# CH32V307VCT6-R0.net
KiCad netlist of a schematic drawn in Altium Designer
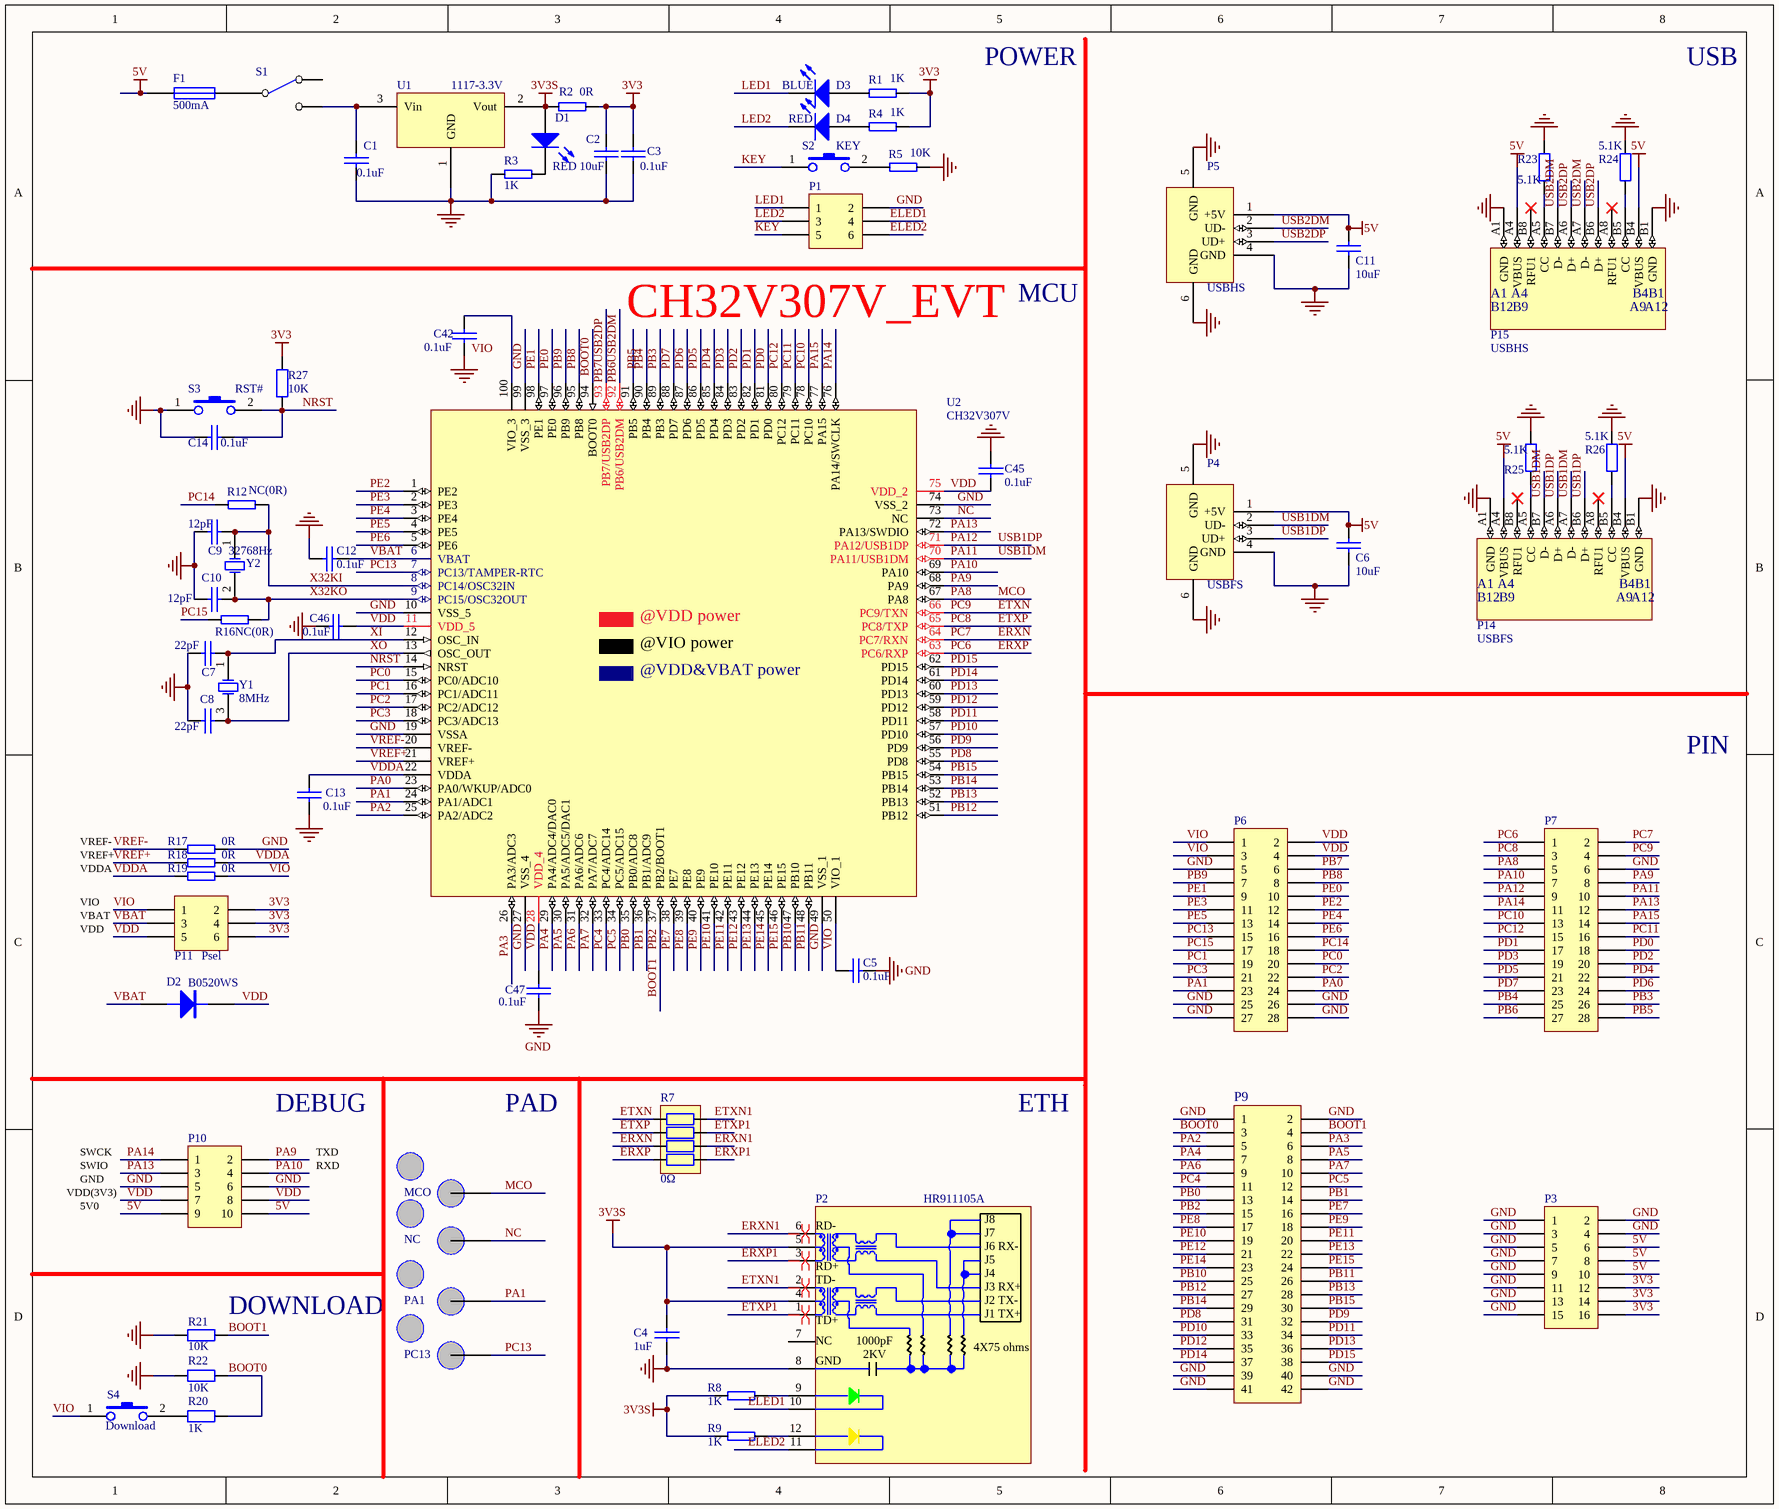
[diagram p0: CH32V307VCT6-R0.SchDoc]

(export (version "E")
  (design (tool "Eeschema 10.0.6"))
  (components
    (comp (ref "C1")
      (value "0.1uF")
      (footprint "0603_C")
      (description "Capacitor")
      (libsource (lib "*") (part "CAP"))
    )
    (comp (ref "C2")
      (value "10uF")
      (footprint "3216_C")
      (description "Capacitor")
      (libsource (lib "*") (part "CAP"))
    )
    (comp (ref "C3")
      (value "0.1uF")
      (footprint "0603_C")
      (description "Capacitor")
      (libsource (lib "*") (part "CAP"))
    )
    (comp (ref "C4")
      (value "1uF")
      (footprint "0603_C")
      (description "Capacitor")
      (libsource (lib "*") (part "CAP"))
    )
    (comp (ref "C5")
      (value "0.1uF")
      (footprint "0603_C")
      (description "Capacitor")
      (libsource (lib "*") (part "CAP"))
    )
    (comp (ref "C6")
      (value "10uF")
      (footprint "3216_C")
      (description "Capacitor")
      (libsource (lib "") (part "CAP_1"))
    )
    (comp (ref "C7")
      (value "22pF")
      (footprint "0603_C")
      (description "Capacitor")
      (libsource (lib "*") (part "CAP"))
    )
    (comp (ref "C8")
      (value "22pF")
      (footprint "0603_C")
      (description "Capacitor")
      (libsource (lib "*") (part "CAP"))
    )
    (comp (ref "C9")
      (value "12pF")
      (footprint "0603_C")
      (description "Capacitor")
      (libsource (lib "*") (part "CAP"))
    )
    (comp (ref "C10")
      (value "12pF")
      (footprint "0603_C")
      (description "Capacitor")
      (libsource (lib "*") (part "CAP"))
    )
    (comp (ref "C11")
      (value "10uF")
      (footprint "3216_C")
      (description "Capacitor")
      (libsource (lib "") (part "CAP_1"))
    )
    (comp (ref "C12")
      (value "0.1uF")
      (footprint "0603_C")
      (description "Capacitor")
      (libsource (lib "*") (part "CAP"))
    )
    (comp (ref "C13")
      (value "0.1uF")
      (footprint "0603_C")
      (description "Capacitor")
      (libsource (lib "*") (part "CAP"))
    )
    (comp (ref "C14")
      (value "0.1uF")
      (footprint "0603_C")
      (description "Capacitor")
      (libsource (lib "") (part "CAP_1"))
    )
    (comp (ref "C42")
      (value "0.1uF")
      (footprint "0603_C")
      (description "Capacitor")
      (libsource (lib "*") (part "CAP"))
    )
    (comp (ref "C45")
      (value "0.1uF")
      (footprint "0603_C")
      (description "Capacitor")
      (libsource (lib "*") (part "CAP"))
    )
    (comp (ref "C46")
      (value "0.1uF")
      (footprint "0603_C")
      (description "Capacitor")
      (libsource (lib "*") (part "CAP"))
    )
    (comp (ref "C47")
      (value "0.1uF")
      (footprint "0603_C")
      (description "Capacitor")
      (libsource (lib "*") (part "CAP"))
    )
    (comp (ref "D1")
      (value "RED")
      (footprint "0603+")
      (description "Typical INFRARED GaAs LED")
      (fields (field (name "PUBLISHER") "Altium Limited"))
      (libsource (lib "*") (part "LED0"))
    )
    (comp (ref "D2")
      (value "B0520WS")
      (footprint "SOD-323")
      (description "Diode")
      (libsource (lib "*") (part "DIODE"))
    )
    (comp (ref "D3")
      (value "BLUE")
      (footprint "0603+")
      (description "Typical INFRARED GaAs LED")
      (fields (field (name "PUBLISHER") "Altium Limited"))
      (libsource (lib "*") (part "LED0"))
    )
    (comp (ref "D4")
      (value "RED")
      (footprint "0603+")
      (description "Typical INFRARED GaAs LED")
      (fields (field (name "PUBLISHER") "Altium Limited"))
      (libsource (lib "*") (part "LED0"))
    )
    (comp (ref "F1")
      (value "500mA")
      (footprint "0805")
      (description "Fuse")
      (libsource (lib "wch_sch_others") (part "FUSE1"))
    )
    (comp (ref "MCO")
      (value "Testpoint")
      (footprint "TESTPOINT1")
      (description "测试点")
      (libsource (lib "wch_sch_others") (part "Testpoint"))
    )
    (comp (ref "NC")
      (value "Testpoint")
      (footprint "TESTPOINT1")
      (description "测试点")
      (libsource (lib "wch_sch_others") (part "Testpoint"))
    )
    (comp (ref "P1")
      (value "IO")
      (footprint "IDC6-2.54mm")
      (description "Header, 3-Pin, Dual row, Right Angle")
      (fields (field (name "PUBLISHER") "Altium Limited"))
      (libsource (lib "Miscellaneous Connectors") (part "Header 3X2H"))
    )
    (comp (ref "P2") (value "HR911105A") (footprint "HR911105A") (libsource (lib "*") (part "HR911105A")))
    (comp (ref "P3")
      (value "Ppin")
      (footprint "IDC16-2.54mm")
      (description "Header, 8-Pin, Dual row, Right Angle")
      (fields (field (name "PUBLISHER") "Altium Limited"))
      (libsource (lib "Miscellaneous Connectors") (part "Header 8X2H"))
    )
    (comp (ref "P4")
      (value "USBFS")
      (footprint "USBAF")
      (description "USB Port")
      (libsource (lib "*") (part "USB"))
    )
    (comp (ref "P5")
      (value "USBHS")
      (footprint "USBAF")
      (description "USB Port")
      (libsource (lib "*") (part "USB"))
    )
    (comp (ref "P6")
      (value "HEADER 14x2")
      (footprint "MYPCB:IDC28-2.54MM")
      (description "Header, 14-Pin, Dual row")
      (libsource (lib "wch_sch_others") (part "HEADER 14x2"))
    )
    (comp (ref "P7")
      (value "HEADER 14x2")
      (footprint "MYPCB:IDC28-2.54MM")
      (description "Header, 14-Pin, Dual row")
      (libsource (lib "wch_sch_others") (part "HEADER 14x2"))
    )
    (comp (ref "P9")
      (value "HEADER 21x2")
      (footprint "MYPCB:IDC42-2.54MM")
      (description "Header, 21-Pin, Dual row")
      (libsource (lib "wch_sch_others") (part "HEADER 21x2"))
    )
    (comp (ref "P10")
      (value "LINK")
      (footprint "IDC10-2.54mm")
      (description "Header, 5-Pin, Dual row, Right Angle")
      (fields (field (name "PUBLISHER") "Altium Limited"))
      (libsource (lib "Miscellaneous Connectors") (part "Header 5X2H"))
    )
    (comp (ref "P11")
      (value "Psel")
      (footprint "IDC6-2.54mm")
      (description "Header, 3-Pin, Dual row, Right Angle")
      (fields (field (name "PUBLISHER") "Altium Limited"))
      (libsource (lib "Miscellaneous Connectors") (part "Header 3X2H"))
    )
    (comp (ref "P14")
      (value "USBFS")
      (footprint "TYPE-C-Receptacle-2.0")
      (libsource (lib "*") (part "TYPE-C1"))
    )
    (comp (ref "P15")
      (value "USBHS")
      (footprint "TYPE-C-Receptacle-2.0")
      (libsource (lib "*") (part "TYPE-C1"))
    )
    (comp (ref "PA1")
      (value "Testpoint")
      (footprint "TESTPOINT1")
      (description "测试点")
      (libsource (lib "wch_sch_others") (part "Testpoint"))
    )
    (comp (ref "PC13")
      (value "Testpoint")
      (footprint "TESTPOINT1")
      (description "测试点")
      (libsource (lib "wch_sch_others") (part "Testpoint"))
    )
    (comp (ref "R1") (value "1K") (footprint "0603") (libsource (lib "wch_sch_others") (part "RES")))
    (comp (ref "R2") (value "0R") (footprint "0603") (libsource (lib "wch_sch_others") (part "RES")))
    (comp (ref "R3") (value "1K") (footprint "0603") (libsource (lib "wch_sch_others") (part "RES")))
    (comp (ref "R4") (value "1K") (footprint "0603") (libsource (lib "wch_sch_others") (part "RES")))
    (comp (ref "R5") (value "10K") (footprint "0603") (libsource (lib "wch_sch_others") (part "RES")))
    (comp (ref "R7")
      (value "0Ω")
      (footprint "RCA-8P4R-0603")
      (description "贴片网络排阻")
      (fields (field (name "版权归属") "源创客"))
      (libsource (lib "wch_sch_others") (part "R-8P4R"))
    )
    (comp (ref "R8") (value "1K") (footprint "0603") (libsource (lib "wch_sch_others") (part "RES")))
    (comp (ref "R9") (value "1K") (footprint "0603") (libsource (lib "wch_sch_others") (part "RES")))
    (comp (ref "R12") (value "NC(0R)") (footprint "0603") (libsource (lib "wch_sch_others") (part "RES")))
    (comp (ref "R16") (value "NC(0R)") (footprint "0603") (libsource (lib "wch_sch_others") (part "RES")))
    (comp (ref "R17") (value "0R") (footprint "0603") (libsource (lib "*") (part "R")))
    (comp (ref "R18") (value "0R") (footprint "0603") (libsource (lib "*") (part "R")))
    (comp (ref "R19") (value "0R") (footprint "0603") (libsource (lib "*") (part "R")))
    (comp (ref "R20")
      (value "1K")
      (footprint "0603")
      (description "Resistor")
      (fields (field (name "PUBLISHER") "Altium Limited"))
      (libsource (lib "") (part "Res2_1"))
    )
    (comp (ref "R21")
      (value "10K")
      (footprint "0603")
      (description "Resistor")
      (fields (field (name "PUBLISHER") "Altium Limited"))
      (libsource (lib "") (part "Res2_1"))
    )
    (comp (ref "R22")
      (value "10K")
      (footprint "0603")
      (description "Resistor")
      (fields (field (name "PUBLISHER") "Altium Limited"))
      (libsource (lib "") (part "Res2_1"))
    )
    (comp (ref "R23")
      (value "5.1K")
      (footprint "0603")
      (description "Resistor")
      (libsource (lib "Miscellaneous Devices") (part "Res2"))
    )
    (comp (ref "R24")
      (value "5.1K")
      (footprint "0603")
      (description "Resistor")
      (libsource (lib "Miscellaneous Devices") (part "Res2"))
    )
    (comp (ref "R25")
      (value "5.1K")
      (footprint "0603")
      (description "Resistor")
      (libsource (lib "Miscellaneous Devices") (part "Res2"))
    )
    (comp (ref "R26")
      (value "5.1K")
      (footprint "0603")
      (description "Resistor")
      (libsource (lib "Miscellaneous Devices") (part "Res2"))
    )
    (comp (ref "R27")
      (value "10K")
      (footprint "0603")
      (description "Resistor")
      (fields (field (name "PUBLISHER") "Altium Limited"))
      (libsource (lib "Miscellaneous Devices") (part "Res2"))
    )
    (comp (ref "S1") (value "SW SPDT") (footprint "KEY_B") (libsource (lib "*") (part "SW SPDT")))
    (comp (ref "S2")
      (value "KEY")
      (footprint "SMD_6.1x3.65x2.5mm-KEY")
      (libsource (lib "wch_sch_others") (part "KEY1"))
    )
    (comp (ref "S3")
      (value "RST#")
      (footprint "SMD_6.1x3.65x2.5mm-KEY")
      (libsource (lib "wch_sch_others") (part "KEY1"))
    )
    (comp (ref "S4")
      (value "Download")
      (footprint "SMD_6.1x3.65x2.5mm-KEY")
      (libsource (lib "wch_sch_others") (part "KEY1"))
    )
    (comp (ref "U1")
      (value "1117-3.3V")
      (footprint "SOT-223")
      (libsource (lib "wch_sch_others") (part "1117-3.3V"))
    )
    (comp (ref "U2")
      (value "CH32V307V")
      (footprint "LQFP100")
      (description "RISC-V FPU HD-MCU, 144MHz, USB_480M, USB OTG, 1000M Ethernet MAC, 2*CAN, FSMC+DVP")
      (libsource (lib "CHXXX") (part "CH32V307V"))
    )
    (comp (ref "Y1")
      (value "8MHz")
      (footprint "XT3225")
      (description "Crystal Oscillator")
      (fields (field (name "PUBLISHER") "Altium Limited"))
      (libsource (lib "*") (part "XTAL"))
    )
    (comp (ref "Y2")
      (value "32768Hz")
      (footprint "FC-135")
      (description "Crystal Oscillator")
      (fields (field (name "PUBLISHER") "Altium Limited"))
      (libsource (lib "") (part "XTAL_1"))
    )
  )
  (nets
    (net (code "2") (name "/BOOT0") (class "Default")
      (node (ref "P9") (pin "3") (pinfunction "3_3") (pintype "passive"))
      (node (ref "R20") (pin "1") (pinfunction "1_1") (pintype "passive"))
      (node (ref "R22") (pin "1") (pinfunction "1_1") (pintype "passive"))
      (node (ref "U2") (pin "94") (pinfunction "BOOT0_94") (pintype "input"))
    )
    (net (code "3") (name "/BOOT1") (class "Default")
      (node (ref "P9") (pin "15") (pinfunction "15_15") (pintype "passive"))
      (node (ref "P9") (pin "4") (pinfunction "4_4") (pintype "passive"))
      (node (ref "R21") (pin "1") (pinfunction "1_1") (pintype "passive"))
      (node (ref "U2") (pin "37") (pinfunction "PB2/BOOT1_37") (pintype "bidirectional"))
    )
    (net (code "4") (name "/ELED1") (class "Default")
      (node (ref "P1") (pin "4") (pinfunction "4_4") (pintype "passive"))
      (node (ref "P2") (pin "10") (pintype "passive"))
    )
    (net (code "5") (name "/ELED2") (class "Default")
      (node (ref "P1") (pin "6") (pinfunction "6_6") (pintype "passive"))
      (node (ref "P2") (pin "11") (pintype "passive"))
    )
    (net (code "6") (name "/ERXN") (class "Default")
      (node (ref "P7") (pin "2") (pinfunction "2_2") (pintype "passive"))
      (node (ref "R7") (pin "3") (pinfunction "3_3") (pintype "passive"))
      (node (ref "U2") (pin "64") (pinfunction "PC7/RXN_64") (pintype "bidirectional"))
    )
    (net (code "7") (name "/ERXN1") (class "Default")
      (node (ref "P2") (pin "6") (pintype "passive"))
      (node (ref "R7") (pin "6") (pinfunction "6_6") (pintype "passive"))
    )
    (net (code "8") (name "/ERXP") (class "Default")
      (node (ref "P7") (pin "1") (pinfunction "1_1") (pintype "passive"))
      (node (ref "R7") (pin "4") (pinfunction "4_4") (pintype "passive"))
      (node (ref "U2") (pin "63") (pinfunction "PC6/RXP_63") (pintype "bidirectional"))
    )
    (net (code "9") (name "/ERXP1") (class "Default")
      (node (ref "P2") (pin "3") (pintype "passive"))
      (node (ref "R7") (pin "5") (pinfunction "5_5") (pintype "passive"))
    )
    (net (code "10") (name "/ETXN") (class "Default")
      (node (ref "P7") (pin "4") (pinfunction "4_4") (pintype "passive"))
      (node (ref "R7") (pin "1") (pinfunction "1_1") (pintype "passive"))
      (node (ref "U2") (pin "66") (pinfunction "PC9/TXN_66") (pintype "bidirectional"))
    )
    (net (code "11") (name "/ETXN1") (class "Default")
      (node (ref "P2") (pin "2") (pintype "passive"))
      (node (ref "R7") (pin "8") (pinfunction "8_8") (pintype "passive"))
    )
    (net (code "12") (name "/ETXP") (class "Default")
      (node (ref "P7") (pin "3") (pinfunction "3_3") (pintype "passive"))
      (node (ref "R7") (pin "2") (pinfunction "2_2") (pintype "passive"))
      (node (ref "U2") (pin "65") (pinfunction "PC8/TXP_65") (pintype "bidirectional"))
    )
    (net (code "13") (name "/ETXP1") (class "Default")
      (node (ref "P2") (pin "1") (pintype "passive"))
      (node (ref "R7") (pin "7") (pinfunction "7_7") (pintype "passive"))
    )
    (net (code "14") (name "/KEY") (class "Default")
      (node (ref "P1") (pin "5") (pinfunction "5_5") (pintype "passive"))
      (node (ref "S2") (pin "1") (pinfunction "1_1") (pintype "passive"))
    )
    (net (code "15") (name "/LED1") (class "Default")
      (node (ref "D3") (pin "2") (pinfunction "K_2") (pintype "passive"))
      (node (ref "P1") (pin "1") (pinfunction "1_1") (pintype "passive"))
    )
    (net (code "16") (name "/LED2") (class "Default")
      (node (ref "D4") (pin "2") (pinfunction "K_2") (pintype "passive"))
      (node (ref "P1") (pin "3") (pinfunction "3_3") (pintype "passive"))
    )
    (net (code "17") (name "/MCO") (class "Default")
      (node (ref "MCO") (pin "1") (pinfunction "point_1") (pintype "passive"))
      (node (ref "P7") (pin "5") (pinfunction "5_5") (pintype "passive"))
      (node (ref "U2") (pin "67") (pinfunction "PA8_67") (pintype "bidirectional"))
    )
    (net (code "18") (name "/NC") (class "Default")
      (node (ref "NC") (pin "1") (pinfunction "point_1") (pintype "passive"))
      (node (ref "U2") (pin "73") (pinfunction "NC_73") (pintype "tri_state"))
    )
    (net (code "19") (name "/NRST") (class "Default")
      (node (ref "C14") (pin "2") (pinfunction "2_2") (pintype "passive"))
      (node (ref "R27") (pin "1") (pinfunction "1_1") (pintype "passive"))
      (node (ref "S3") (pin "2") (pinfunction "2_2") (pintype "passive"))
      (node (ref "U2") (pin "14") (pinfunction "NRST_14") (pintype "input"))
    )
    (net (code "20") (name "/PA0") (class "Default")
      (node (ref "P6") (pin "24") (pinfunction "24_24") (pintype "passive"))
      (node (ref "U2") (pin "23") (pinfunction "PA0/WKUP/ADC0_23") (pintype "bidirectional"))
    )
    (net (code "21") (name "/PA1") (class "Default")
      (node (ref "P6") (pin "23") (pinfunction "23_23") (pintype "passive"))
      (node (ref "PA1") (pin "1") (pinfunction "point_1") (pintype "passive"))
      (node (ref "U2") (pin "24") (pinfunction "PA1/ADC1_24") (pintype "bidirectional"))
    )
    (net (code "22") (name "/PA2") (class "Default")
      (node (ref "P9") (pin "5") (pinfunction "5_5") (pintype "passive"))
      (node (ref "U2") (pin "25") (pinfunction "PA2/ADC2_25") (pintype "bidirectional"))
    )
    (net (code "23") (name "/PA3") (class "Default")
      (node (ref "P9") (pin "6") (pinfunction "6_6") (pintype "passive"))
      (node (ref "U2") (pin "26") (pinfunction "PA3/ADC3_26") (pintype "bidirectional"))
    )
    (net (code "24") (name "/PA4") (class "Default")
      (node (ref "P9") (pin "7") (pinfunction "7_7") (pintype "passive"))
      (node (ref "U2") (pin "29") (pinfunction "PA4/ADC4/DAC0_29") (pintype "bidirectional"))
    )
    (net (code "25") (name "/PA5") (class "Default")
      (node (ref "P9") (pin "8") (pinfunction "8_8") (pintype "passive"))
      (node (ref "U2") (pin "30") (pinfunction "PA5/ADC5/DAC1_30") (pintype "bidirectional"))
    )
    (net (code "26") (name "/PA6") (class "Default")
      (node (ref "P9") (pin "9") (pinfunction "9_9") (pintype "passive"))
      (node (ref "U2") (pin "31") (pinfunction "PA6/ADC6_31") (pintype "bidirectional"))
    )
    (net (code "27") (name "/PA7") (class "Default")
      (node (ref "P9") (pin "10") (pinfunction "10_10") (pintype "passive"))
      (node (ref "U2") (pin "32") (pinfunction "PA7/ADC7_32") (pintype "bidirectional"))
    )
    (net (code "28") (name "/PA9") (class "Default")
      (node (ref "P10") (pin "2") (pinfunction "2_2") (pintype "passive"))
      (node (ref "P7") (pin "8") (pinfunction "8_8") (pintype "passive"))
      (node (ref "U2") (pin "68") (pinfunction "PA9_68") (pintype "bidirectional"))
    )
    (net (code "29") (name "/PA10") (class "Default")
      (node (ref "P10") (pin "4") (pinfunction "4_4") (pintype "passive"))
      (node (ref "P7") (pin "7") (pinfunction "7_7") (pintype "passive"))
      (node (ref "U2") (pin "69") (pinfunction "PA10_69") (pintype "bidirectional"))
    )
    (net (code "30") (name "/PA11") (class "Default")
      (node (ref "P14") (pin "A7") (pinfunction "D-_A7") (pintype "bidirectional"))
      (node (ref "P14") (pin "B7") (pinfunction "D-_B7") (pintype "bidirectional"))
      (node (ref "P4") (pin "2") (pinfunction "UD-_2") (pintype "bidirectional"))
      (node (ref "P7") (pin "10") (pinfunction "10_10") (pintype "passive"))
      (node (ref "U2") (pin "70") (pinfunction "PA11/USB1DM_70") (pintype "bidirectional"))
    )
    (net (code "31") (name "/PA12") (class "Default")
      (node (ref "P14") (pin "A6") (pinfunction "D+_A6") (pintype "bidirectional"))
      (node (ref "P14") (pin "B6") (pinfunction "D+_B6") (pintype "bidirectional"))
      (node (ref "P4") (pin "3") (pinfunction "UD+_3") (pintype "bidirectional"))
      (node (ref "P7") (pin "9") (pinfunction "9_9") (pintype "passive"))
      (node (ref "U2") (pin "71") (pinfunction "PA12/USB1DP_71") (pintype "bidirectional"))
    )
    (net (code "32") (name "/PA13") (class "Default")
      (node (ref "P10") (pin "3") (pinfunction "3_3") (pintype "passive"))
      (node (ref "P7") (pin "12") (pinfunction "12_12") (pintype "passive"))
      (node (ref "U2") (pin "72") (pinfunction "PA13/SWDIO_72") (pintype "bidirectional"))
    )
    (net (code "33") (name "/PA14") (class "Default")
      (node (ref "P10") (pin "1") (pinfunction "1_1") (pintype "passive"))
      (node (ref "P7") (pin "11") (pinfunction "11_11") (pintype "passive"))
      (node (ref "U2") (pin "76") (pinfunction "PA14/SWCLK_76") (pintype "bidirectional"))
    )
    (net (code "34") (name "/PA15") (class "Default")
      (node (ref "P7") (pin "14") (pinfunction "14_14") (pintype "passive"))
      (node (ref "U2") (pin "77") (pinfunction "PA15_77") (pintype "bidirectional"))
    )
    (net (code "35") (name "/PB0") (class "Default")
      (node (ref "P9") (pin "13") (pinfunction "13_13") (pintype "passive"))
      (node (ref "U2") (pin "35") (pinfunction "PB0/ADC8_35") (pintype "bidirectional"))
    )
    (net (code "36") (name "/PB1") (class "Default")
      (node (ref "P9") (pin "14") (pinfunction "14_14") (pintype "passive"))
      (node (ref "U2") (pin "36") (pinfunction "PB1/ADC9_36") (pintype "bidirectional"))
    )
    (net (code "37") (name "/PB3") (class "Default")
      (node (ref "P7") (pin "26") (pinfunction "26_26") (pintype "passive"))
      (node (ref "U2") (pin "89") (pinfunction "PB3_89") (pintype "bidirectional"))
    )
    (net (code "38") (name "/PB4") (class "Default")
      (node (ref "P7") (pin "25") (pinfunction "25_25") (pintype "passive"))
      (node (ref "U2") (pin "90") (pinfunction "PB4_90") (pintype "bidirectional"))
    )
    (net (code "39") (name "/PB5") (class "Default")
      (node (ref "P7") (pin "28") (pinfunction "28_28") (pintype "passive"))
    )
    (net (code "40") (name "/PB6") (class "Default")
      (node (ref "P15") (pin "A7") (pinfunction "D-_A7") (pintype "bidirectional"))
      (node (ref "P15") (pin "B7") (pinfunction "D-_B7") (pintype "bidirectional"))
      (node (ref "P5") (pin "2") (pinfunction "UD-_2") (pintype "bidirectional"))
      (node (ref "P7") (pin "27") (pinfunction "27_27") (pintype "passive"))
      (node (ref "U2") (pin "92") (pinfunction "PB6/USB2DM_92") (pintype "bidirectional"))
    )
    (net (code "41") (name "/PB7") (class "Default")
      (node (ref "P15") (pin "A6") (pinfunction "D+_A6") (pintype "bidirectional"))
      (node (ref "P15") (pin "B6") (pinfunction "D+_B6") (pintype "bidirectional"))
      (node (ref "P5") (pin "3") (pinfunction "UD+_3") (pintype "bidirectional"))
      (node (ref "P6") (pin "6") (pinfunction "6_6") (pintype "passive"))
      (node (ref "U2") (pin "93") (pinfunction "PB7/USB2DP_93") (pintype "bidirectional"))
    )
    (net (code "42") (name "/PB8") (class "Default")
      (node (ref "P6") (pin "8") (pinfunction "8_8") (pintype "passive"))
      (node (ref "U2") (pin "95") (pinfunction "PB8_95") (pintype "bidirectional"))
    )
    (net (code "43") (name "/PB9") (class "Default")
      (node (ref "P6") (pin "7") (pinfunction "7_7") (pintype "passive"))
      (node (ref "U2") (pin "96") (pinfunction "PB9_96") (pintype "bidirectional"))
    )
    (net (code "44") (name "/PB10") (class "Default")
      (node (ref "P9") (pin "25") (pinfunction "25_25") (pintype "passive"))
      (node (ref "U2") (pin "47") (pinfunction "PB10_47") (pintype "bidirectional"))
    )
    (net (code "45") (name "/PB11") (class "Default")
      (node (ref "P9") (pin "26") (pinfunction "26_26") (pintype "passive"))
      (node (ref "U2") (pin "48") (pinfunction "PB11_48") (pintype "bidirectional"))
    )
    (net (code "46") (name "/PB12") (class "Default")
      (node (ref "P9") (pin "27") (pinfunction "27_27") (pintype "passive"))
      (node (ref "U2") (pin "51") (pinfunction "PB12_51") (pintype "bidirectional"))
    )
    (net (code "47") (name "/PB13") (class "Default")
      (node (ref "P9") (pin "28") (pinfunction "28_28") (pintype "passive"))
      (node (ref "U2") (pin "52") (pinfunction "PB13_52") (pintype "bidirectional"))
    )
    (net (code "48") (name "/PB14") (class "Default")
      (node (ref "P9") (pin "29") (pinfunction "29_29") (pintype "passive"))
      (node (ref "U2") (pin "53") (pinfunction "PB14_53") (pintype "bidirectional"))
    )
    (net (code "49") (name "/PB15") (class "Default")
      (node (ref "P9") (pin "30") (pinfunction "30_30") (pintype "passive"))
      (node (ref "U2") (pin "54") (pinfunction "PB15_54") (pintype "bidirectional"))
    )
    (net (code "50") (name "/PC0") (class "Default")
      (node (ref "P6") (pin "20") (pinfunction "20_20") (pintype "passive"))
      (node (ref "U2") (pin "15") (pinfunction "PC0/ADC10_15") (pintype "bidirectional"))
    )
    (net (code "51") (name "/PC1") (class "Default")
      (node (ref "P6") (pin "19") (pinfunction "19_19") (pintype "passive"))
      (node (ref "U2") (pin "16") (pinfunction "PC1/ADC11_16") (pintype "bidirectional"))
    )
    (net (code "52") (name "/PC2") (class "Default")
      (node (ref "P6") (pin "22") (pinfunction "22_22") (pintype "passive"))
      (node (ref "U2") (pin "17") (pinfunction "PC2/ADC12_17") (pintype "bidirectional"))
    )
    (net (code "53") (name "/PC3") (class "Default")
      (node (ref "P6") (pin "21") (pinfunction "21_21") (pintype "passive"))
      (node (ref "U2") (pin "18") (pinfunction "PC3/ADC13_18") (pintype "bidirectional"))
    )
    (net (code "54") (name "/PC4") (class "Default")
      (node (ref "P9") (pin "11") (pinfunction "11_11") (pintype "passive"))
      (node (ref "U2") (pin "33") (pinfunction "PC4/ADC14_33") (pintype "bidirectional"))
    )
    (net (code "55") (name "/PC5") (class "Default")
      (node (ref "P9") (pin "12") (pinfunction "12_12") (pintype "passive"))
      (node (ref "U2") (pin "34") (pinfunction "PC5/ADC15_34") (pintype "bidirectional"))
    )
    (net (code "56") (name "/PC10") (class "Default")
      (node (ref "P7") (pin "13") (pinfunction "13_13") (pintype "passive"))
      (node (ref "U2") (pin "78") (pinfunction "PC10_78") (pintype "bidirectional"))
    )
    (net (code "57") (name "/PC11") (class "Default")
      (node (ref "P7") (pin "16") (pinfunction "16_16") (pintype "passive"))
      (node (ref "U2") (pin "79") (pinfunction "PC11_79") (pintype "bidirectional"))
    )
    (net (code "58") (name "/PC12") (class "Default")
      (node (ref "P7") (pin "15") (pinfunction "15_15") (pintype "passive"))
      (node (ref "U2") (pin "80") (pinfunction "PC12_80") (pintype "bidirectional"))
    )
    (net (code "59") (name "/PC13") (class "Default")
      (node (ref "P6") (pin "15") (pinfunction "15_15") (pintype "passive"))
      (node (ref "PC13") (pin "1") (pinfunction "point_1") (pintype "passive"))
      (node (ref "U2") (pin "7") (pinfunction "PC13/TAMPER-RTC_7") (pintype "bidirectional"))
    )
    (net (code "60") (name "/PC14") (class "Default")
      (node (ref "P6") (pin "18") (pinfunction "18_18") (pintype "passive"))
      (node (ref "R12") (pin "1") (pintype "passive"))
    )
    (net (code "61") (name "/PC15") (class "Default")
      (node (ref "P6") (pin "17") (pinfunction "17_17") (pintype "passive"))
      (node (ref "R16") (pin "1") (pintype "passive"))
    )
    (net (code "62") (name "/PD0") (class "Default")
      (node (ref "P7") (pin "18") (pinfunction "18_18") (pintype "passive"))
      (node (ref "U2") (pin "81") (pinfunction "PD0_81") (pintype "bidirectional"))
    )
    (net (code "63") (name "/PD1") (class "Default")
      (node (ref "P7") (pin "17") (pinfunction "17_17") (pintype "passive"))
      (node (ref "U2") (pin "82") (pinfunction "PD1_82") (pintype "bidirectional"))
    )
    (net (code "64") (name "/PD2") (class "Default")
      (node (ref "P7") (pin "20") (pinfunction "20_20") (pintype "passive"))
      (node (ref "U2") (pin "83") (pinfunction "PD2_83") (pintype "bidirectional"))
    )
    (net (code "65") (name "/PD3") (class "Default")
      (node (ref "P7") (pin "19") (pinfunction "19_19") (pintype "passive"))
      (node (ref "U2") (pin "84") (pinfunction "PD3_84") (pintype "bidirectional"))
    )
    (net (code "66") (name "/PD4") (class "Default")
      (node (ref "P7") (pin "22") (pinfunction "22_22") (pintype "passive"))
      (node (ref "U2") (pin "85") (pinfunction "PD4_85") (pintype "bidirectional"))
    )
    (net (code "67") (name "/PD5") (class "Default")
      (node (ref "P7") (pin "21") (pinfunction "21_21") (pintype "passive"))
      (node (ref "U2") (pin "86") (pinfunction "PD5_86") (pintype "bidirectional"))
    )
    (net (code "68") (name "/PD6") (class "Default")
      (node (ref "P7") (pin "24") (pinfunction "24_24") (pintype "passive"))
      (node (ref "U2") (pin "87") (pinfunction "PD6_87") (pintype "bidirectional"))
    )
    (net (code "69") (name "/PD7") (class "Default")
      (node (ref "P7") (pin "23") (pinfunction "23_23") (pintype "passive"))
      (node (ref "U2") (pin "88") (pinfunction "PD7_88") (pintype "bidirectional"))
    )
    (net (code "70") (name "/PD8") (class "Default")
      (node (ref "P9") (pin "31") (pinfunction "31_31") (pintype "passive"))
      (node (ref "U2") (pin "55") (pinfunction "PD8_55") (pintype "bidirectional"))
    )
    (net (code "71") (name "/PD9") (class "Default")
      (node (ref "P9") (pin "32") (pinfunction "32_32") (pintype "passive"))
      (node (ref "U2") (pin "56") (pinfunction "PD9_56") (pintype "bidirectional"))
    )
    (net (code "72") (name "/PD10") (class "Default")
      (node (ref "P9") (pin "33") (pinfunction "33_33") (pintype "passive"))
      (node (ref "U2") (pin "57") (pinfunction "PD10_57") (pintype "bidirectional"))
    )
    (net (code "73") (name "/PD11") (class "Default")
      (node (ref "P9") (pin "34") (pinfunction "34_34") (pintype "passive"))
      (node (ref "U2") (pin "58") (pinfunction "PD11_58") (pintype "bidirectional"))
    )
    (net (code "74") (name "/PD12") (class "Default")
      (node (ref "P9") (pin "35") (pinfunction "35_35") (pintype "passive"))
      (node (ref "U2") (pin "59") (pinfunction "PD12_59") (pintype "bidirectional"))
    )
    (net (code "75") (name "/PD13") (class "Default")
      (node (ref "P9") (pin "36") (pinfunction "36_36") (pintype "passive"))
      (node (ref "U2") (pin "60") (pinfunction "PD13_60") (pintype "bidirectional"))
    )
    (net (code "76") (name "/PD14") (class "Default")
      (node (ref "P9") (pin "37") (pinfunction "37_37") (pintype "passive"))
      (node (ref "U2") (pin "61") (pinfunction "PD14_61") (pintype "bidirectional"))
    )
    (net (code "77") (name "/PD15") (class "Default")
      (node (ref "P9") (pin "38") (pinfunction "38_38") (pintype "passive"))
      (node (ref "U2") (pin "62") (pinfunction "PD15_62") (pintype "bidirectional"))
    )
    (net (code "78") (name "/PE0") (class "Default")
      (node (ref "P6") (pin "10") (pinfunction "10_10") (pintype "passive"))
      (node (ref "U2") (pin "97") (pinfunction "PE0_97") (pintype "bidirectional"))
    )
    (net (code "79") (name "/PE1") (class "Default")
      (node (ref "P6") (pin "9") (pinfunction "9_9") (pintype "passive"))
      (node (ref "U2") (pin "98") (pinfunction "PE1_98") (pintype "bidirectional"))
    )
    (net (code "80") (name "/PE2") (class "Default")
      (node (ref "P6") (pin "12") (pinfunction "12_12") (pintype "passive"))
      (node (ref "U2") (pin "1") (pinfunction "PE2_1") (pintype "bidirectional"))
    )
    (net (code "81") (name "/PE3") (class "Default")
      (node (ref "P6") (pin "11") (pinfunction "11_11") (pintype "passive"))
      (node (ref "U2") (pin "2") (pinfunction "PE3_2") (pintype "bidirectional"))
    )
    (net (code "82") (name "/PE4") (class "Default")
      (node (ref "P6") (pin "14") (pinfunction "14_14") (pintype "passive"))
      (node (ref "U2") (pin "3") (pinfunction "PE4_3") (pintype "bidirectional"))
    )
    (net (code "83") (name "/PE5") (class "Default")
      (node (ref "P6") (pin "13") (pinfunction "13_13") (pintype "passive"))
      (node (ref "U2") (pin "4") (pinfunction "PE5_4") (pintype "bidirectional"))
    )
    (net (code "84") (name "/PE6") (class "Default")
      (node (ref "P6") (pin "16") (pinfunction "16_16") (pintype "passive"))
      (node (ref "U2") (pin "5") (pinfunction "PE6_5") (pintype "bidirectional"))
    )
    (net (code "85") (name "/PE7") (class "Default")
      (node (ref "P9") (pin "16") (pinfunction "16_16") (pintype "passive"))
      (node (ref "U2") (pin "38") (pinfunction "PE7_38") (pintype "bidirectional"))
    )
    (net (code "86") (name "/PE8") (class "Default")
      (node (ref "P9") (pin "17") (pinfunction "17_17") (pintype "passive"))
      (node (ref "U2") (pin "39") (pinfunction "PE8_39") (pintype "bidirectional"))
    )
    (net (code "87") (name "/PE9") (class "Default")
      (node (ref "P9") (pin "18") (pinfunction "18_18") (pintype "passive"))
      (node (ref "U2") (pin "40") (pinfunction "PE9_40") (pintype "bidirectional"))
    )
    (net (code "88") (name "/PE10") (class "Default")
      (node (ref "P9") (pin "19") (pinfunction "19_19") (pintype "passive"))
      (node (ref "U2") (pin "41") (pinfunction "PE10_41") (pintype "bidirectional"))
    )
    (net (code "89") (name "/PE11") (class "Default")
      (node (ref "P9") (pin "20") (pinfunction "20_20") (pintype "passive"))
      (node (ref "U2") (pin "42") (pinfunction "PE11_42") (pintype "bidirectional"))
    )
    (net (code "90") (name "/PE12") (class "Default")
      (node (ref "P9") (pin "21") (pinfunction "21_21") (pintype "passive"))
      (node (ref "U2") (pin "43") (pinfunction "PE12_43") (pintype "bidirectional"))
    )
    (net (code "91") (name "/PE13") (class "Default")
      (node (ref "P9") (pin "22") (pinfunction "22_22") (pintype "passive"))
      (node (ref "U2") (pin "44") (pinfunction "PE13_44") (pintype "bidirectional"))
    )
    (net (code "92") (name "/PE14") (class "Default")
      (node (ref "P9") (pin "23") (pinfunction "23_23") (pintype "passive"))
      (node (ref "U2") (pin "45") (pinfunction "PE14_45") (pintype "bidirectional"))
    )
    (net (code "93") (name "/PE15") (class "Default")
      (node (ref "P9") (pin "24") (pinfunction "24_24") (pintype "passive"))
      (node (ref "U2") (pin "46") (pinfunction "PE15_46") (pintype "bidirectional"))
    )
    (net (code "94") (name "/VBAT") (class "Default")
      (node (ref "C12") (pin "2") (pinfunction "2_2") (pintype "passive"))
      (node (ref "D2") (pin "1") (pinfunction "A_1") (pintype "passive"))
      (node (ref "P11") (pin "3") (pinfunction "3_3") (pintype "passive"))
      (node (ref "U2") (pin "6") (pinfunction "VBAT_6") (pintype "power_in"))
    )
    (net (code "95") (name "/VDD") (class "Default")
      (node (ref "C45") (pin "1") (pinfunction "1_1") (pintype "passive"))
      (node (ref "C46") (pin "1") (pinfunction "1_1") (pintype "passive"))
      (node (ref "C47") (pin "2") (pinfunction "2_2") (pintype "passive"))
      (node (ref "D2") (pin "2") (pinfunction "K_2") (pintype "passive"))
      (node (ref "P10") (pin "7") (pinfunction "7_7") (pintype "passive"))
      (node (ref "P10") (pin "8") (pinfunction "8_8") (pintype "passive"))
      (node (ref "P11") (pin "5") (pinfunction "5_5") (pintype "passive"))
      (node (ref "P6") (pin "2") (pinfunction "2_2") (pintype "passive"))
      (node (ref "P6") (pin "4") (pinfunction "4_4") (pintype "passive"))
      (node (ref "U2") (pin "11") (pinfunction "VDD_5_11") (pintype "power_in"))
      (node (ref "U2") (pin "28") (pinfunction "VDD_4_28") (pintype "power_in"))
      (node (ref "U2") (pin "75") (pinfunction "VDD_2_75") (pintype "power_in"))
    )
    (net (code "96") (name "/VDDA") (class "Default")
      (node (ref "C13") (pin "1") (pinfunction "1_1") (pintype "passive"))
      (node (ref "R18") (pin "1") (pinfunction "1_1") (pintype "passive"))
      (node (ref "R19") (pin "2") (pinfunction "2_2") (pintype "passive"))
      (node (ref "U2") (pin "22") (pinfunction "VDDA_22") (pintype "power_in"))
    )
    (net (code "97") (name "/VIO") (class "Default")
      (node (ref "C5") (pin "1") (pinfunction "1_1") (pintype "passive"))
      (node (ref "P11") (pin "1") (pinfunction "1_1") (pintype "passive"))
      (node (ref "P6") (pin "1") (pinfunction "1_1") (pintype "passive"))
      (node (ref "P6") (pin "3") (pinfunction "3_3") (pintype "passive"))
      (node (ref "R19") (pin "1") (pinfunction "1_1") (pintype "passive"))
      (node (ref "S4") (pin "1") (pinfunction "1_1") (pintype "passive"))
      (node (ref "U2") (pin "50") (pinfunction "VIO_1_50") (pintype "power_in"))
    )
    (net (code "98") (name "/VREF+") (class "Default")
      (node (ref "R18") (pin "2") (pinfunction "2_2") (pintype "passive"))
      (node (ref "U2") (pin "21") (pinfunction "VREF+_21") (pintype "power_in"))
    )
    (net (code "99") (name "/VREF-") (class "Default")
      (node (ref "R17") (pin "2") (pinfunction "2_2") (pintype "passive"))
      (node (ref "U2") (pin "20") (pinfunction "VREF-_20") (pintype "power_in"))
    )
    (net (code "100") (name "/X32KI") (class "Default")
      (node (ref "C9") (pin "2") (pinfunction "2_2") (pintype "passive"))
      (node (ref "R12") (pin "2") (pintype "passive"))
      (node (ref "U2") (pin "8") (pinfunction "PC14/OSC32IN_8") (pintype "bidirectional"))
      (node (ref "Y2") (pin "1") (pinfunction "OSC1_1") (pintype "passive"))
    )
    (net (code "101") (name "/X32KO") (class "Default")
      (node (ref "C10") (pin "2") (pinfunction "2_2") (pintype "passive"))
      (node (ref "R16") (pin "2") (pintype "passive"))
      (node (ref "U2") (pin "9") (pinfunction "PC15/OSC32OUT_9") (pintype "bidirectional"))
      (node (ref "Y2") (pin "2") (pinfunction "OSC2_2") (pintype "passive"))
    )
    (net (code "102") (name "/XI") (class "Default")
      (node (ref "C7") (pin "2") (pinfunction "2_2") (pintype "passive"))
      (node (ref "U2") (pin "12") (pinfunction "OSC_IN_12") (pintype "input"))
      (node (ref "Y1") (pin "1") (pinfunction "OSC1_1") (pintype "passive"))
    )
    (net (code "103") (name "/XO") (class "Default")
      (node (ref "C8") (pin "2") (pinfunction "2_2") (pintype "passive"))
      (node (ref "U2") (pin "13") (pinfunction "OSC_OUT_13") (pintype "output"))
      (node (ref "Y1") (pin "3") (pinfunction "OSC2_3") (pintype "passive"))
    )
    (net (code "104") (name "3V3") (class "Default")
      (node (ref "C2") (pin "1") (pinfunction "1_1") (pintype "passive"))
      (node (ref "C3") (pin "1") (pinfunction "1_1") (pintype "passive"))
      (node (ref "P11") (pin "2") (pinfunction "2_2") (pintype "passive"))
      (node (ref "P11") (pin "4") (pinfunction "4_4") (pintype "passive"))
      (node (ref "P11") (pin "6") (pinfunction "6_6") (pintype "passive"))
      (node (ref "P3") (pin "12") (pinfunction "12_12") (pintype "passive"))
      (node (ref "P3") (pin "14") (pinfunction "14_14") (pintype "passive"))
      (node (ref "P3") (pin "16") (pinfunction "16_16") (pintype "passive"))
      (node (ref "R1") (pin "1") (pintype "passive"))
      (node (ref "R2") (pin "1") (pintype "passive"))
      (node (ref "R27") (pin "2") (pinfunction "2_2") (pintype "passive"))
      (node (ref "R4") (pin "1") (pintype "passive"))
    )
    (net (code "105") (name "3V3S") (class "Default")
      (node (ref "C4") (pin "2") (pinfunction "2_2") (pintype "passive"))
      (node (ref "D1") (pin "1") (pinfunction "A_1") (pintype "passive"))
      (node (ref "P2") (pin "4") (pintype "passive"))
      (node (ref "P2") (pin "5") (pintype "passive"))
      (node (ref "R2") (pin "2") (pintype "passive"))
      (node (ref "R8") (pin "1") (pintype "passive"))
      (node (ref "R9") (pin "1") (pintype "passive"))
      (node (ref "U1") (pin "2") (pinfunction "Vout_2") (pintype "passive"))
    )
    (net (code "106") (name "5V") (class "Default")
      (node (ref "C11") (pin "1") (pinfunction "1_1") (pintype "passive"))
      (node (ref "C6") (pin "1") (pinfunction "1_1") (pintype "passive"))
      (node (ref "F1") (pin "1") (pinfunction "1_1") (pintype "passive"))
      (node (ref "P10") (pin "10") (pinfunction "10_10") (pintype "passive"))
      (node (ref "P10") (pin "9") (pinfunction "9_9") (pintype "passive"))
      (node (ref "P14") (pin "A4") (pinfunction "VBUS_A4") (pintype "bidirectional"))
      (node (ref "P14") (pin "B4") (pinfunction "VBUS_B4") (pintype "bidirectional"))
      (node (ref "P15") (pin "A4") (pinfunction "VBUS_A4") (pintype "bidirectional"))
      (node (ref "P15") (pin "B4") (pinfunction "VBUS_B4") (pintype "bidirectional"))
      (node (ref "P3") (pin "10") (pinfunction "10_10") (pintype "passive"))
      (node (ref "P3") (pin "6") (pinfunction "6_6") (pintype "passive"))
      (node (ref "P3") (pin "8") (pinfunction "8_8") (pintype "passive"))
      (node (ref "P4") (pin "1") (pinfunction "+5V_1") (pintype "power_in"))
      (node (ref "P5") (pin "1") (pinfunction "+5V_1") (pintype "power_in"))
    )
    (net (code "107") (name "GND") (class "Default")
      (node (ref "C1") (pin "2") (pinfunction "2_2") (pintype "passive"))
      (node (ref "C10") (pin "1") (pinfunction "1_1") (pintype "passive"))
      (node (ref "C11") (pin "2") (pinfunction "2_2") (pintype "passive"))
      (node (ref "C12") (pin "1") (pinfunction "1_1") (pintype "passive"))
      (node (ref "C13") (pin "2") (pinfunction "2_2") (pintype "passive"))
      (node (ref "C14") (pin "1") (pinfunction "1_1") (pintype "passive"))
      (node (ref "C2") (pin "2") (pinfunction "2_2") (pintype "passive"))
      (node (ref "C3") (pin "2") (pinfunction "2_2") (pintype "passive"))
      (node (ref "C4") (pin "1") (pinfunction "1_1") (pintype "passive"))
      (node (ref "C42") (pin "1") (pinfunction "1_1") (pintype "passive"))
      (node (ref "C45") (pin "2") (pinfunction "2_2") (pintype "passive"))
      (node (ref "C46") (pin "2") (pinfunction "2_2") (pintype "passive"))
      (node (ref "C47") (pin "1") (pinfunction "1_1") (pintype "passive"))
      (node (ref "C5") (pin "2") (pinfunction "2_2") (pintype "passive"))
      (node (ref "C6") (pin "2") (pinfunction "2_2") (pintype "passive"))
      (node (ref "C7") (pin "1") (pinfunction "1_1") (pintype "passive"))
      (node (ref "C8") (pin "1") (pinfunction "1_1") (pintype "passive"))
      (node (ref "C9") (pin "1") (pinfunction "1_1") (pintype "passive"))
      (node (ref "P1") (pin "2") (pinfunction "2_2") (pintype "passive"))
      (node (ref "P10") (pin "5") (pinfunction "5_5") (pintype "passive"))
      (node (ref "P10") (pin "6") (pinfunction "6_6") (pintype "passive"))
      (node (ref "P14") (pin "A1") (pinfunction "GND_A1") (pintype "bidirectional"))
      (node (ref "P14") (pin "B1") (pinfunction "GND_B1") (pintype "bidirectional"))
      (node (ref "P15") (pin "A1") (pinfunction "GND_A1") (pintype "bidirectional"))
      (node (ref "P15") (pin "B1") (pinfunction "GND_B1") (pintype "bidirectional"))
      (node (ref "P2") (pin "8") (pintype "passive"))
      (node (ref "P3") (pin "1") (pinfunction "1_1") (pintype "passive"))
      (node (ref "P3") (pin "11") (pinfunction "11_11") (pintype "passive"))
      (node (ref "P3") (pin "13") (pinfunction "13_13") (pintype "passive"))
      (node (ref "P3") (pin "15") (pinfunction "15_15") (pintype "passive"))
      (node (ref "P3") (pin "2") (pinfunction "2_2") (pintype "passive"))
      (node (ref "P3") (pin "3") (pinfunction "3_3") (pintype "passive"))
      (node (ref "P3") (pin "4") (pinfunction "4_4") (pintype "passive"))
      (node (ref "P3") (pin "5") (pinfunction "5_5") (pintype "passive"))
      (node (ref "P3") (pin "7") (pinfunction "7_7") (pintype "passive"))
      (node (ref "P3") (pin "9") (pinfunction "9_9") (pintype "passive"))
      (node (ref "P4") (pin "4") (pinfunction "GND_4") (pintype "power_in"))
      (node (ref "P4") (pin "5") (pinfunction "GND_5") (pintype "power_in"))
      (node (ref "P4") (pin "6") (pinfunction "GND_6") (pintype "power_in"))
      (node (ref "P5") (pin "4") (pinfunction "GND_4") (pintype "power_in"))
      (node (ref "P5") (pin "5") (pinfunction "GND_5") (pintype "power_in"))
      (node (ref "P5") (pin "6") (pinfunction "GND_6") (pintype "power_in"))
      (node (ref "P6") (pin "25") (pinfunction "25_25") (pintype "passive"))
      (node (ref "P6") (pin "26") (pinfunction "26_26") (pintype "passive"))
      (node (ref "P6") (pin "27") (pinfunction "27_27") (pintype "passive"))
      (node (ref "P6") (pin "28") (pinfunction "28_28") (pintype "passive"))
      (node (ref "P6") (pin "5") (pinfunction "5_5") (pintype "passive"))
      (node (ref "P7") (pin "6") (pinfunction "6_6") (pintype "passive"))
      (node (ref "P9") (pin "1") (pinfunction "1_1") (pintype "passive"))
      (node (ref "P9") (pin "2") (pinfunction "2_2") (pintype "passive"))
      (node (ref "P9") (pin "39") (pinfunction "39_39") (pintype "passive"))
      (node (ref "P9") (pin "40") (pinfunction "40_40") (pintype "passive"))
      (node (ref "P9") (pin "41") (pinfunction "41_41") (pintype "passive"))
      (node (ref "P9") (pin "42") (pinfunction "42_42") (pintype "passive"))
      (node (ref "R17") (pin "1") (pinfunction "1_1") (pintype "passive"))
      (node (ref "R21") (pin "2") (pinfunction "2_2") (pintype "passive"))
      (node (ref "R22") (pin "2") (pinfunction "2_2") (pintype "passive"))
      (node (ref "R23") (pin "2") (pinfunction "2_2") (pintype "passive"))
      (node (ref "R24") (pin "2") (pinfunction "2_2") (pintype "passive"))
      (node (ref "R25") (pin "2") (pinfunction "2_2") (pintype "passive"))
      (node (ref "R26") (pin "2") (pinfunction "2_2") (pintype "passive"))
      (node (ref "R3") (pin "2") (pintype "passive"))
      (node (ref "R5") (pin "1") (pintype "passive"))
      (node (ref "S3") (pin "1") (pinfunction "1_1") (pintype "passive"))
      (node (ref "U1") (pin "1") (pinfunction "GND_1") (pintype "passive"))
      (node (ref "U2") (pin "10") (pinfunction "VSS_5_10") (pintype "power_in"))
      (node (ref "U2") (pin "19") (pinfunction "VSSA_19") (pintype "power_in"))
      (node (ref "U2") (pin "27") (pinfunction "VSS_4_27") (pintype "power_in"))
      (node (ref "U2") (pin "49") (pinfunction "VSS_1_49") (pintype "power_in"))
      (node (ref "U2") (pin "74") (pinfunction "VSS_2_74") (pintype "power_in"))
      (node (ref "U2") (pin "99") (pinfunction "VSS_3_99") (pintype "power_in"))
    )
    (net (code "108") (name "Net-(D1-K)") (class "Default")
      (node (ref "D1") (pin "2") (pinfunction "K_2") (pintype "passive"))
      (node (ref "R3") (pin "1") (pintype "passive"))
    )
    (net (code "109") (name "Net-(D3-A)") (class "Default")
      (node (ref "D3") (pin "1") (pinfunction "A_1") (pintype "passive"))
      (node (ref "R1") (pin "2") (pintype "passive"))
    )
    (net (code "110") (name "Net-(D4-A)") (class "Default")
      (node (ref "D4") (pin "1") (pinfunction "A_1") (pintype "passive"))
      (node (ref "R4") (pin "2") (pintype "passive"))
    )
    (net (code "111") (name "Net-(P2-Pad9)") (class "Default")
      (node (ref "P2") (pin "9") (pintype "passive"))
      (node (ref "R8") (pin "2") (pintype "passive"))
    )
    (net (code "112") (name "Net-(P2-Pad12)") (class "Default")
      (node (ref "P2") (pin "12") (pintype "passive"))
      (node (ref "R9") (pin "2") (pintype "passive"))
    )
    (net (code "113") (name "Net-(P14-CC-PadA5)") (class "Default")
      (node (ref "P14") (pin "A5") (pinfunction "CC_A5") (pintype "bidirectional"))
      (node (ref "R25") (pin "1") (pinfunction "1_1") (pintype "passive"))
    )
    (net (code "114") (name "Net-(P14-CC-PadB5)") (class "Default")
      (node (ref "P14") (pin "B5") (pinfunction "CC_B5") (pintype "bidirectional"))
      (node (ref "R26") (pin "1") (pinfunction "1_1") (pintype "passive"))
    )
    (net (code "115") (name "Net-(P15-CC-PadA5)") (class "Default")
      (node (ref "P15") (pin "A5") (pinfunction "CC_A5") (pintype "bidirectional"))
      (node (ref "R23") (pin "1") (pinfunction "1_1") (pintype "passive"))
    )
    (net (code "116") (name "Net-(P15-CC-PadB5)") (class "Default")
      (node (ref "P15") (pin "B5") (pinfunction "CC_B5") (pintype "bidirectional"))
      (node (ref "R24") (pin "1") (pinfunction "1_1") (pintype "passive"))
    )
    (net (code "117") (name "Net-(R5-Pad2)") (class "Default")
      (node (ref "R5") (pin "2") (pintype "passive"))
      (node (ref "S2") (pin "2") (pinfunction "2_2") (pintype "passive"))
    )
    (net (code "118") (name "Net-(R20-Pad2)") (class "Default")
      (node (ref "R20") (pin "2") (pinfunction "2_2") (pintype "passive"))
      (node (ref "S4") (pin "2") (pinfunction "2_2") (pintype "passive"))
    )
    (net (code "119") (name "Net-(S1-COMMON)") (class "Default")
      (node (ref "F1") (pin "2") (pinfunction "2_2") (pintype "passive"))
      (node (ref "S1") (pin "1") (pinfunction "COMMON_1") (pintype "passive"))
    )
    (net (code "120") (name "Net-(S1-NC)") (class "Default")
      (node (ref "C1") (pin "1") (pinfunction "1_1") (pintype "passive"))
      (node (ref "S1") (pin "2") (pinfunction "NC_2") (pintype "passive"))
      (node (ref "U1") (pin "3") (pinfunction "Vin_3") (pintype "passive"))
    )
    (net (code "121") (name "Net-(U2-VIO_3)") (class "Default")
      (node (ref "C42") (pin "2") (pinfunction "2_2") (pintype "passive"))
      (node (ref "U2") (pin "100") (pinfunction "VIO_3_100") (pintype "power_in"))
    )
    (net (code "122") (name "unconnected-(P2-Pad7)") (class "Default")
      (node (ref "P2") (pin "7") (pintype "passive"))
    )
    (net (code "123") (name "unconnected-(P14-RFU1-PadA8)") (class "Default")
      (node (ref "P14") (pin "A8") (pinfunction "RFU1_A8") (pintype "bidirectional+no_connect"))
    )
    (net (code "124") (name "unconnected-(P14-RFU1-PadB8)") (class "Default")
      (node (ref "P14") (pin "B8") (pinfunction "RFU1_B8") (pintype "bidirectional+no_connect"))
    )
    (net (code "125") (name "unconnected-(P15-RFU1-PadA8)") (class "Default")
      (node (ref "P15") (pin "A8") (pinfunction "RFU1_A8") (pintype "bidirectional+no_connect"))
    )
    (net (code "126") (name "unconnected-(P15-RFU1-PadB8)") (class "Default")
      (node (ref "P15") (pin "B8") (pinfunction "RFU1_B8") (pintype "bidirectional+no_connect"))
    )
    (net (code "127") (name "unconnected-(S1-NO-Pad3)") (class "Default")
      (node (ref "S1") (pin "3") (pinfunction "NO_3") (pintype "passive"))
    )
    (net (code "128") (name "unconnected-(U2-PB5-Pad91)") (class "Default")
      (node (ref "U2") (pin "91") (pinfunction "PB5_91") (pintype "bidirectional"))
    )
  )
)
